# RS232.net
KiCad netlist of a schematic drawn in Altium Designer
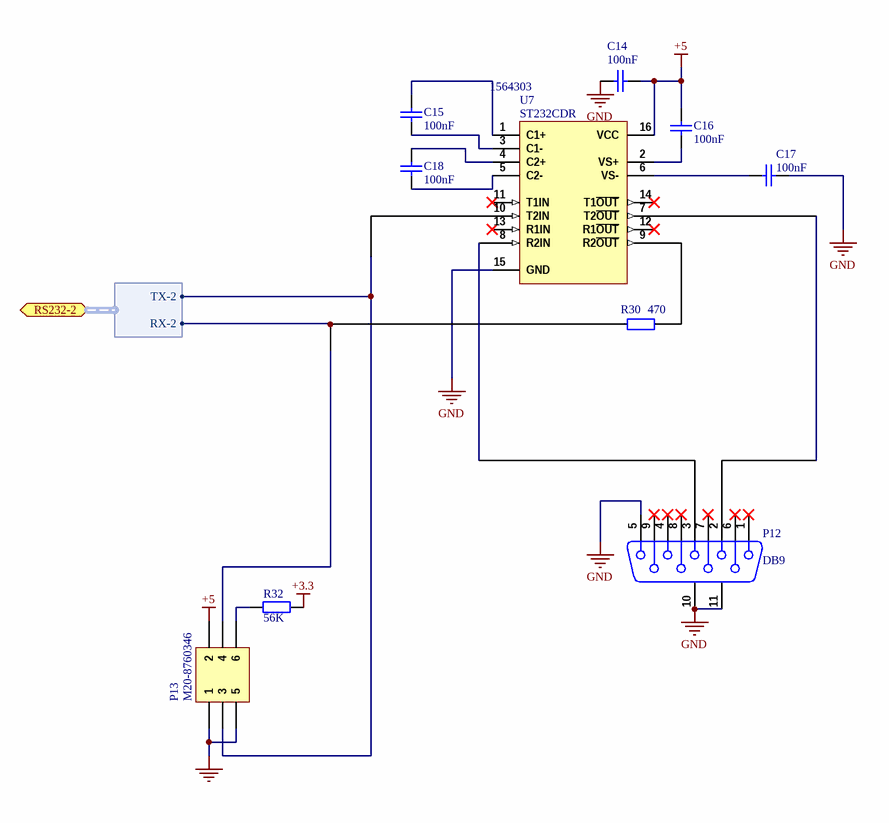
[diagram p0: RS232.SchDoc]

(export (version "E")
  (design (tool "Eeschema 10.0.6"))
  (components
    (comp (ref "C14")
      (value "100nF")
      (footprint "C0805")
      (description "Capacitor")
      (fields
        (field (name "MANUFACTURER") "MULTICOMP")
        (field (name "MANUFACTURER PART NUMBER") "MCCA000296")
      )
      (libsource (lib "Miscellaneous Devices") (part "Cap"))
    )
    (comp (ref "C15")
      (value "100nF")
      (footprint "C0805")
      (description "Capacitor")
      (fields
        (field (name "MANUFACTURER") "MULTICOMP")
        (field (name "MANUFACTURER PART NUMBER") "MCCA000296")
      )
      (libsource (lib "Miscellaneous Devices") (part "Cap"))
    )
    (comp (ref "C16")
      (value "100nF")
      (footprint "C0805")
      (description "Capacitor")
      (fields
        (field (name "MANUFACTURER") "MULTICOMP")
        (field (name "MANUFACTURER PART NUMBER") "MCCA000296")
      )
      (libsource (lib "Miscellaneous Devices") (part "Cap"))
    )
    (comp (ref "C17")
      (value "100nF")
      (footprint "C0805")
      (description "Capacitor")
      (fields
        (field (name "MANUFACTURER") "MULTICOMP")
        (field (name "MANUFACTURER PART NUMBER") "MCCA000296")
      )
      (libsource (lib "Miscellaneous Devices") (part "Cap"))
    )
    (comp (ref "C18")
      (value "100nF")
      (footprint "C0805")
      (description "Capacitor")
      (fields
        (field (name "MANUFACTURER") "MULTICOMP")
        (field (name "MANUFACTURER PART NUMBER") "MCCA000296")
      )
      (libsource (lib "Miscellaneous Devices") (part "Cap"))
    )
    (comp (ref "P12")
      (value "DB9")
      (footprint "SUBD9_F_V")
      (description "Receptacle Assembly, 9 Position, Right Angle")
      (fields
        (field (name "MANUFACTURER") "TE CONNECTIVITY / AMP")
        (field (name "MANUFACTURER PART NUMBER") "2-338313-2")
      )
      (libsource (lib "Miscellaneous Connectors") (part "D Connector 9"))
    )
    (comp (ref "P13")
      (value "M20-8760346")
      (footprint "M20-2X3")
      (description "Header, 3-Pin, Dual row")
      (fields (field (name "MANUFACTURER") "Harwin"))
      (libsource (lib "Miscellaneous Connectors") (part "Header 3X2"))
    )
    (comp (ref "R30")
      (value "470")
      (footprint "R0805")
      (description "Resistor")
      (fields
        (field (name "MANUFACTURER") "MULTICOMP")
        (field (name "MANUFACTURER PART NUMBER") "MC0.1W08051%470RFR")
      )
      (libsource (lib "Miscellaneous Devices") (part "Res2"))
    )
    (comp (ref "R32")
      (value "56K")
      (footprint "R0805")
      (description "Resistor")
      (fields
        (field (name "MANUFACTURER") "MULTICOMP")
        (field (name "MANUFACTURER PART NUMBER") "MC0.1W08051%56KFR")
      )
      (libsource (lib "BRA") (part "Resistor 0805 56K"))
    )
    (comp (ref "U7")
      (value "ST232CDR")
      (footprint "SO-16")
      (description "Dual EIA-232 Driver/Receiver")
      (fields
        (field (name "SUPPLIER PART NUMBER 1") "1564303")
        (field (name "MANUFACTURER") "STMICROELECTRONICS")
      )
      (libsource (lib "TI Interface Line Transceiver") (part "MAX232D"))
    )
  )
  (nets
    (net (code "2") (name "+3.3") (class "Default")
      (node (ref "R32") (pin "2") (pinfunction "2_2") (pintype "passive"))
    )
    (net (code "3") (name "+5") (class "Default")
      (node (ref "C14") (pin "1") (pinfunction "1_1") (pintype "passive"))
      (node (ref "C16") (pin "2") (pinfunction "2_2") (pintype "passive"))
      (node (ref "P13") (pin "2") (pinfunction "2_2") (pintype "passive"))
      (node (ref "U7") (pin "16") (pinfunction "VCC_16") (pintype "power_in"))
    )
    (net (code "5") (name "GND") (class "Default")
      (node (ref "C14") (pin "2") (pinfunction "2_2") (pintype "passive"))
      (node (ref "C17") (pin "1") (pinfunction "1_1") (pintype "passive"))
      (node (ref "P12") (pin "10") (pinfunction "MH1_10") (pintype "passive"))
      (node (ref "P12") (pin "11") (pinfunction "MH2_11") (pintype "passive"))
      (node (ref "P12") (pin "5") (pinfunction "5_5") (pintype "passive"))
      (node (ref "P13") (pin "1") (pinfunction "1_1") (pintype "passive"))
      (node (ref "P13") (pin "5") (pinfunction "5_5") (pintype "passive"))
      (node (ref "U7") (pin "15") (pinfunction "GND_15") (pintype "power_in"))
    )
    (net (code "6") (name "Net-(P13-Pad4)") (class "Default")
      (node (ref "P13") (pin "4") (pinfunction "4_4") (pintype "passive"))
      (node (ref "R30") (pin "1") (pinfunction "1_1") (pintype "passive"))
    )
    (net (code "7") (name "Net-(P13-Pad6)") (class "Default")
      (node (ref "P13") (pin "6") (pinfunction "6_6") (pintype "passive"))
      (node (ref "R32") (pin "1") (pinfunction "1_1") (pintype "passive"))
    )
    (net (code "8") (name "Net-(U7-C1+)") (class "Default")
      (node (ref "C15") (pin "2") (pinfunction "2_2") (pintype "passive"))
      (node (ref "U7") (pin "1") (pinfunction "C1+_1") (pintype "passive"))
    )
    (net (code "9") (name "Net-(U7-C1-)") (class "Default")
      (node (ref "C15") (pin "1") (pinfunction "1_1") (pintype "passive"))
      (node (ref "U7") (pin "3") (pinfunction "C1-_3") (pintype "passive"))
    )
    (net (code "10") (name "Net-(U7-C2+)") (class "Default")
      (node (ref "C18") (pin "2") (pinfunction "2_2") (pintype "passive"))
      (node (ref "U7") (pin "4") (pinfunction "C2+_4") (pintype "passive"))
    )
    (net (code "11") (name "Net-(U7-C2-)") (class "Default")
      (node (ref "C18") (pin "1") (pinfunction "1_1") (pintype "passive"))
      (node (ref "U7") (pin "5") (pinfunction "C2-_5") (pintype "passive"))
    )
    (net (code "12") (name "Net-(U7-R2IN)") (class "Default")
      (node (ref "P12") (pin "3") (pinfunction "3_3") (pintype "passive"))
      (node (ref "U7") (pin "8") (pinfunction "R2IN_8") (pintype "input"))
    )
    (net (code "13") (name "Net-(U7-R2~{OUT})") (class "Default")
      (node (ref "R30") (pin "2") (pinfunction "2_2") (pintype "passive"))
      (node (ref "U7") (pin "9") (pinfunction "R2~{OUT}_9") (pintype "output"))
    )
    (net (code "14") (name "Net-(U7-T2IN)") (class "Default")
      (node (ref "P13") (pin "3") (pinfunction "3_3") (pintype "passive"))
      (node (ref "U7") (pin "10") (pinfunction "T2IN_10") (pintype "input"))
    )
    (net (code "15") (name "Net-(U7-T2~{OUT})") (class "Default")
      (node (ref "P12") (pin "2") (pinfunction "2_2") (pintype "passive"))
      (node (ref "U7") (pin "7") (pinfunction "T2~{OUT}_7") (pintype "output"))
    )
    (net (code "16") (name "Net-(U7-VS+)") (class "Default")
      (node (ref "C16") (pin "1") (pinfunction "1_1") (pintype "passive"))
      (node (ref "U7") (pin "2") (pinfunction "VS+_2") (pintype "power_in"))
    )
    (net (code "17") (name "Net-(U7-VS-)") (class "Default")
      (node (ref "C17") (pin "2") (pinfunction "2_2") (pintype "passive"))
      (node (ref "U7") (pin "6") (pinfunction "VS-_6") (pintype "power_in"))
    )
    (net (code "18") (name "unconnected-(P12-Pad1)") (class "Default")
      (node (ref "P12") (pin "1") (pinfunction "1_1") (pintype "passive+no_connect"))
    )
    (net (code "19") (name "unconnected-(P12-Pad4)") (class "Default")
      (node (ref "P12") (pin "4") (pinfunction "4_4") (pintype "passive+no_connect"))
    )
    (net (code "20") (name "unconnected-(P12-Pad6)") (class "Default")
      (node (ref "P12") (pin "6") (pinfunction "6_6") (pintype "passive+no_connect"))
    )
    (net (code "21") (name "unconnected-(P12-Pad7)") (class "Default")
      (node (ref "P12") (pin "7") (pinfunction "7_7") (pintype "passive+no_connect"))
    )
    (net (code "22") (name "unconnected-(P12-Pad8)") (class "Default")
      (node (ref "P12") (pin "8") (pinfunction "8_8") (pintype "passive+no_connect"))
    )
    (net (code "23") (name "unconnected-(P12-Pad9)") (class "Default")
      (node (ref "P12") (pin "9") (pinfunction "9_9") (pintype "passive+no_connect"))
    )
    (net (code "24") (name "unconnected-(U7-R1IN-Pad13)") (class "Default")
      (node (ref "U7") (pin "13") (pinfunction "R1IN_13") (pintype "input+no_connect"))
    )
    (net (code "25") (name "unconnected-(U7-R1~{OUT}-Pad12)") (class "Default")
      (node (ref "U7") (pin "12") (pinfunction "R1~{OUT}_12") (pintype "output+no_connect"))
    )
    (net (code "26") (name "unconnected-(U7-T1IN-Pad11)") (class "Default")
      (node (ref "U7") (pin "11") (pinfunction "T1IN_11") (pintype "input+no_connect"))
    )
    (net (code "27") (name "unconnected-(U7-T1~{OUT}-Pad14)") (class "Default")
      (node (ref "U7") (pin "14") (pinfunction "T1~{OUT}_14") (pintype "output+no_connect"))
    )
  )
)
